# Key.net
KiCad netlist of a schematic drawn in Altium Designer
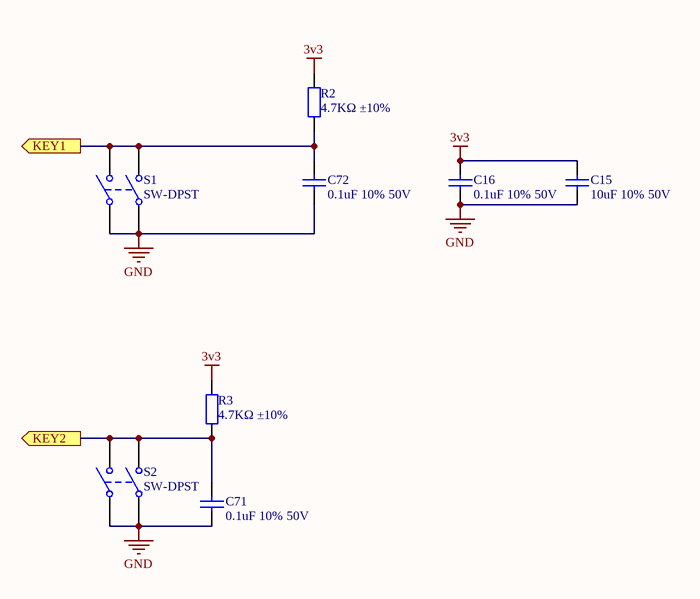
[diagram p0: Key.SchDoc]

(export (version "E")
  (design (tool "Eeschema 10.0.6"))
  (components
    (comp (ref "C15")
      (value "10uF 10% 50V")
      (footprint "0805_C")
      (description "贴片电容")
      (libsource (lib "Cap") (part "0603 4.7uF (475) 10% 16V"))
    )
    (comp (ref "C16")
      (value "0.1uF 10% 50V")
      (footprint "0603_C")
      (description "贴片电容")
      (libsource (lib "Cap") (part "0603 4.7uF (475) 10% 16V"))
    )
    (comp (ref "C71")
      (value "0.1uF 10% 50V")
      (footprint "0603_C")
      (description "贴片电容")
      (libsource (lib "Cap") (part "0603 4.7uF (475) 10% 16V"))
    )
    (comp (ref "C72")
      (value "0.1uF 10% 50V")
      (footprint "0603_C")
      (description "贴片电容")
      (libsource (lib "Cap") (part "0603 4.7uF (475) 10% 16V"))
    )
    (comp (ref "R2")
      (value "4.7KΩ ±10%")
      (footprint "0603_R")
      (description "贴片电阻")
      (libsource (lib "RES") (part "0603 2.2Ω (2R20) 1%"))
    )
    (comp (ref "R3")
      (value "4.7KΩ ±10%")
      (footprint "0603_R")
      (description "贴片电阻")
      (libsource (lib "RES") (part "0603 2.2Ω (2R20) 1%"))
    )
    (comp (ref "S1")
      (value "SW-DPST")
      (footprint "SW1")
      (description "Double-Pole, Single-Throw Switch")
      (fields (field (name "PUBLISHER") "Altium Limited"))
      (libsource (lib "Miscellaneous Devices") (part "SW-DPST"))
    )
    (comp (ref "S2")
      (value "SW-DPST")
      (footprint "SW1")
      (description "Double-Pole, Single-Throw Switch")
      (fields (field (name "PUBLISHER") "Altium Limited"))
      (libsource (lib "Miscellaneous Devices") (part "SW-DPST"))
    )
  )
  (nets
    (net (code "1") (name "/KEY1") (class "Default")
      (node (ref "C72") (pin "2") (pinfunction "2_2") (pintype "passive"))
      (node (ref "R2") (pin "1") (pinfunction "1_1") (pintype "passive"))
      (node (ref "S1") (pin "2") (pinfunction "NO1_2") (pintype "passive"))
      (node (ref "S1") (pin "4") (pinfunction "NO2_4") (pintype "passive"))
    )
    (net (code "2") (name "/KEY2") (class "Default")
      (node (ref "C71") (pin "2") (pinfunction "2_2") (pintype "passive"))
      (node (ref "R3") (pin "1") (pinfunction "1_1") (pintype "passive"))
      (node (ref "S2") (pin "2") (pinfunction "NO1_2") (pintype "passive"))
      (node (ref "S2") (pin "4") (pinfunction "NO2_4") (pintype "passive"))
    )
    (net (code "3") (name "3v3") (class "Default")
      (node (ref "C15") (pin "2") (pinfunction "2_2") (pintype "passive"))
      (node (ref "C16") (pin "2") (pinfunction "2_2") (pintype "passive"))
      (node (ref "R2") (pin "2") (pinfunction "2_2") (pintype "passive"))
      (node (ref "R3") (pin "2") (pinfunction "2_2") (pintype "passive"))
    )
    (net (code "4") (name "GND") (class "Default")
      (node (ref "C15") (pin "1") (pinfunction "1_1") (pintype "passive"))
      (node (ref "C16") (pin "1") (pinfunction "1_1") (pintype "passive"))
      (node (ref "C71") (pin "1") (pinfunction "1_1") (pintype "passive"))
      (node (ref "C72") (pin "1") (pinfunction "1_1") (pintype "passive"))
      (node (ref "S1") (pin "1") (pinfunction "COMMON1_1") (pintype "passive"))
      (node (ref "S1") (pin "3") (pinfunction "COMMON2_3") (pintype "passive"))
      (node (ref "S2") (pin "1") (pinfunction "COMMON1_1") (pintype "passive"))
      (node (ref "S2") (pin "3") (pinfunction "COMMON2_3") (pintype "passive"))
    )
  )
)
